# 7_PowerManagement.net
KiCad netlist of a schematic drawn in Altium Designer
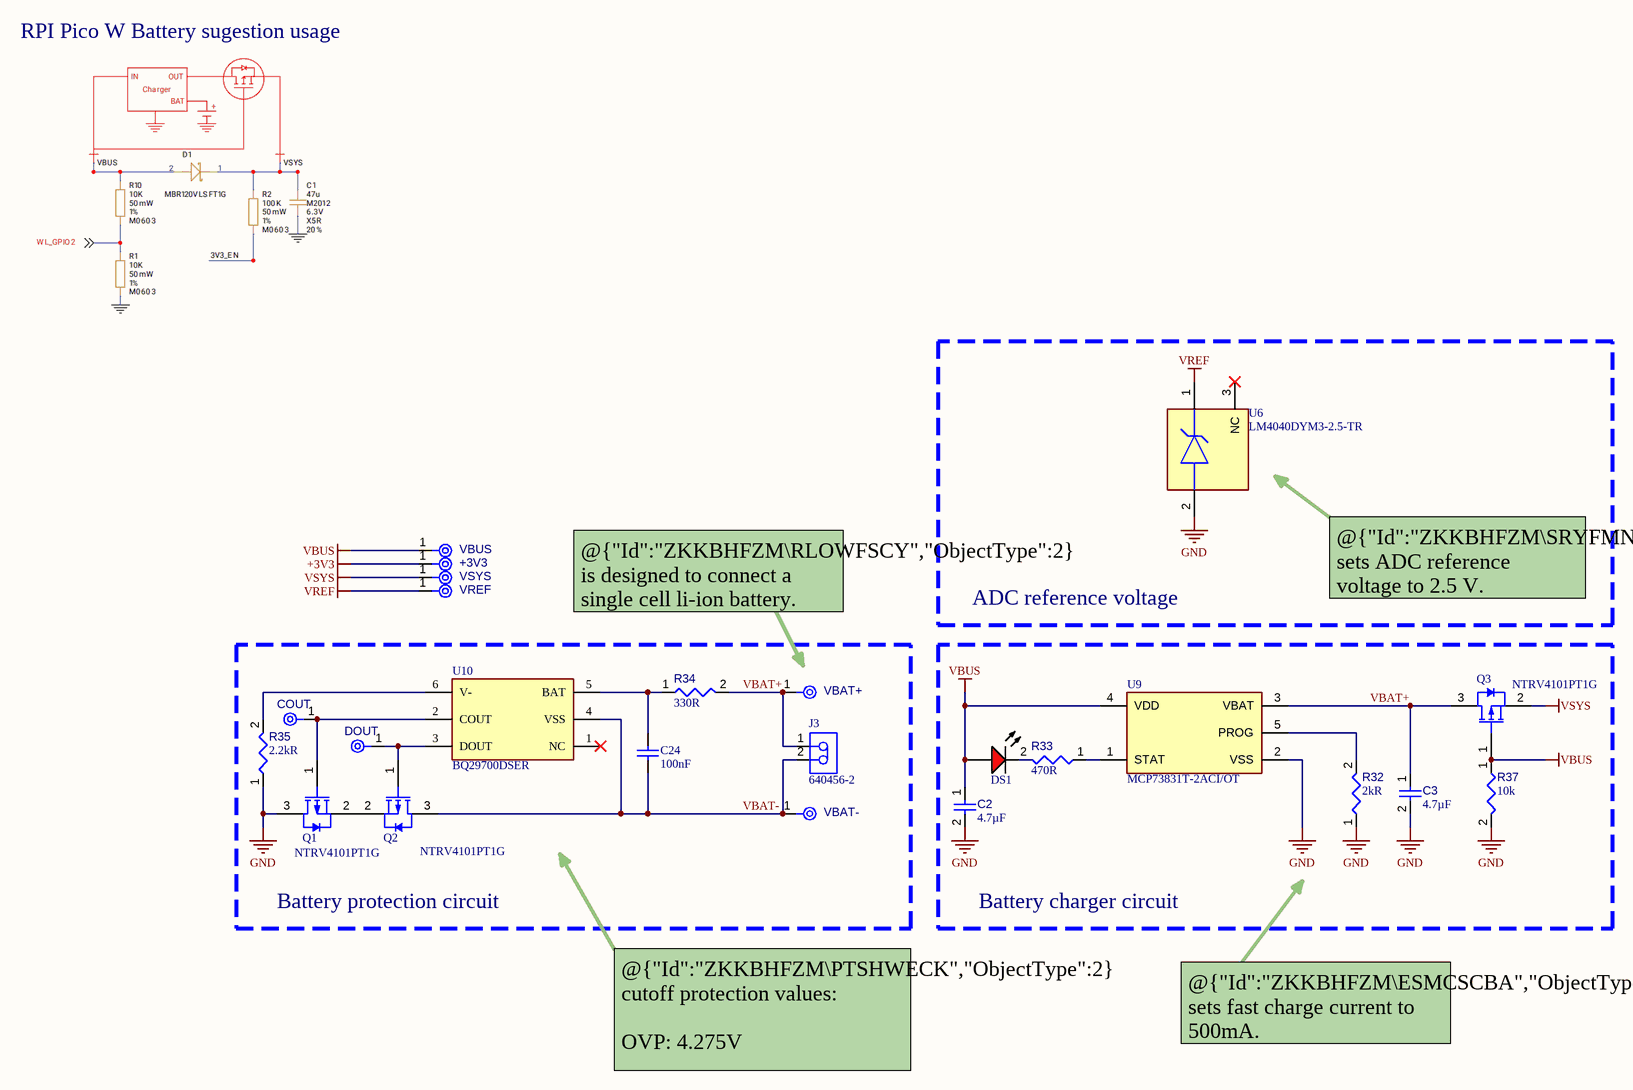
[diagram p0: [7] PowerManagement.SchDoc]

(export (version "E")
  (design (tool "Eeschema 10.0.6"))
  (components
    (comp (ref "+3V3")
      (value "TPAD6R")
      (footprint "TP06R")
      (description "0.6mm round")
      (libsource (lib "UFCG - Universidade Federal de Campina Grande") (part "CMP-001-0001-4"))
    )
    (comp (ref "C2")
      (value "4.7µF")
      (footprint "CAPC0603(1608)100_L")
      (description "Chip Capacitor, 4.7µF +/-20%, 10V, 0603, Thickness 1 mm")
      (fields (field (name "TOLERANCE") "10%") (field (name "Comment") "Capacitor 4.7µF +/-20% 10V 0603"))
      (libsource (lib "UFCG - Universidade Federal de Campina Grande") (part "CAP-NP-2"))
    )
    (comp (ref "C3")
      (value "4.7µF")
      (footprint "CAPC0603(1608)100_L")
      (description "Chip Capacitor, 4.7µF +/-20%, 10V, 0603, Thickness 1 mm")
      (fields (field (name "TOLERANCE") "10%") (field (name "Comment") "Capacitor 4.7µF +/-20% 10V 0603"))
      (libsource (lib "UFCG - Universidade Federal de Campina Grande") (part "CAP-NP-2"))
    )
    (comp (ref "C24")
      (value "100nF")
      (footprint "CAPC0603(1608)100_L")
      (description "Multilayer Ceramic Capacitor, 0.1 uF, 16 V, ± 20%, X7R, 0603 [1608 Metric]")
      (fields (field (name "TOLERANCE") "20%") (field (name "Comment") "VJ0603Y104MXJCW1BC"))
      (libsource (lib "UFCG - Universidade Federal de Campina Grande") (part "CAP"))
    )
    (comp (ref "COUT")
      (value "TPAD6R")
      (footprint "TP06R")
      (description "0.6mm round")
      (libsource (lib "UFCG - Universidade Federal de Campina Grande") (part "CMP-001-0001-4"))
    )
    (comp (ref "DOUT")
      (value "TPAD6R")
      (footprint "TP06R")
      (description "0.6mm round")
      (libsource (lib "UFCG - Universidade Federal de Campina Grande") (part "CMP-001-0001-4"))
    )
    (comp (ref "DS1")
      (value "19-217/R6C-AL1M2VY/3T")
      (footprint "EVRL-0603-2_V")
      (description "Chip LED, Red, 5 V, 25 mA, -40 to 85 degC, 2-Pin SMD (0603), RoHS, Tape and Reel")
      (fields (field (name "MANUFACTURER") "Everlight Electronics"))
      (libsource (lib "UFCG - Universidade Federal de Campina Grande") (part "LED-RED-AK-2"))
    )
    (comp (ref "J3")
      (value "640456-2")
      (footprint "TECO-640456-2_V")
      (description "Connector 250V AC/DC 5A 2P 1 Row PCB - Vertical Mounting Polyester White")
      (libsource (lib "UFCG - Universidade Federal de Campina Grande") (part "CN-2P-F-QF2"))
    )
    (comp (ref "Q1")
      (value "NTRV4101PT1G")
      (footprint "ONSC-SOT-23-3-318-08_V")
      (description "NTRV4101PT1G P-channel MOSFET Transistor; 1.7 A; 20 V; 3-Pin SOT-23")
      (libsource (lib "UFCG - Universidade Federal de Campina Grande") (part "ONSC-PMOS-G1S2D3-3_D"))
    )
    (comp (ref "Q2")
      (value "NTRV4101PT1G")
      (footprint "ONSC-SOT-23-3-318-08_V")
      (description "NTRV4101PT1G P-channel MOSFET Transistor; 1.7 A; 20 V; 3-Pin SOT-23")
      (libsource (lib "UFCG - Universidade Federal de Campina Grande") (part "ONSC-PMOS-G1S2D3-3_D"))
    )
    (comp (ref "Q3")
      (value "NTRV4101PT1G")
      (footprint "ONSC-SOT-23-3-318-08_V")
      (description "NTRV4101PT1G P-channel MOSFET Transistor; 1.7 A; 20 V; 3-Pin SOT-23")
      (libsource (lib "UFCG - Universidade Federal de Campina Grande") (part "ONSC-PMOS-G1S2D3-3_D"))
    )
    (comp (ref "R32")
      (value "2kR")
      (footprint "RESC0603(1608)_L")
      (description "SMD Chip Resistor, 2 kOhm, ï¿½ 1%, 100 mW, 0603 [1608 Metric], Thick Film, Precision")
      (fields (field (name "TOLERANCE") "1%") (field (name "Comment") "ERJ-3EKF2001V"))
      (libsource (lib "UFCG - Universidade Federal de Campina Grande") (part "RES-2"))
    )
    (comp (ref "R33")
      (value "470R")
      (footprint "RESC0603(1608)_L")
      (description "Res Thick Film 0603 470 Ohm 5% 0.1W(1/10W) ±200ppm/°C Pad SMD Automotive T/R")
      (fields (field (name "TOLERANCE") "5%") (field (name "Comment") "CRCW0603470RJNEA"))
      (libsource (lib "UFCG - Universidade Federal de Campina Grande") (part "RES-2"))
    )
    (comp (ref "R34")
      (value "330R")
      (footprint "RESC0603(1608)_L")
      (description "SMD Chip Resistor, 330 Ohm, ± 1%, 100 mW, 0603 [1608 Metric], Thick Film, Precision")
      (fields (field (name "TOLERANCE") "1%") (field (name "Comment") "ERJ-3EKF3300V"))
      (libsource (lib "UFCG - Universidade Federal de Campina Grande") (part "RES-2"))
    )
    (comp (ref "R35")
      (value "2.2kR")
      (footprint "RESC0603(1608)_L")
      (description "SMD Chip Resistor, 2.2 kOhm, ± 1%, 100 mW, 0603 [1608 Metric], Thick Film, General Purpose")
      (fields (field (name "TOLERANCE") "1%") (field (name "Comment") "CRCW06032K20FKEA"))
      (libsource (lib "UFCG - Universidade Federal de Campina Grande") (part "RES-2"))
    )
    (comp (ref "R37")
      (value "10k")
      (footprint "RESC0603(1608)_L")
      (description "Chip Resistor, 10 KOhm, +/- 1%, 01 W, -55 to 155 degC, 0603 (1608 Metric)")
      (fields (field (name "POWER") "100mW") (field (name "TOLERANCE") "1%"))
      (libsource (lib "UFCG - Universidade Federal de Campina Grande") (part "RES-2"))
    )
    (comp (ref "U6")
      (value "LM4040DYM3-2.5-TR")
      (footprint "FP-SOT23-3LD-PL-1-IPC_A")
      (description "LM4040 Series 2.5 V ±1 % Precision Micropower Shunt Voltage Reference - SOT-23")
      (fields (field (name "TOLERANCE") "1%"))
      (libsource (lib "UFCG - Universidade Federal de Campina Grande") (part "91f0ca7be5727739b22823fb575e884"))
    )
    (comp (ref "U9")
      (value "MCP73831T-2ACI/OT")
      (footprint "FP-C04-091-OT-MFG")
      (description "MCP73831 Series Single-Cell Li-Ion/Li-Polymer Battery Charge Controller SOT-23-5")
      (libsource (lib "UFCG - Universidade Federal de Campina Grande") (part "61f5a3bb3429d9e0caadea342aa3b19"))
    )
    (comp (ref "U10")
      (value "BQ29700DSER")
      (footprint "FP-DSE0006A-MFG")
      (description "Li-Ion/Li Polymer Advanced Single-Cell Battery Protector IC Family 6-WSON -40 to 85")
      (libsource (lib "UFCG - Universidade Federal de Campina Grande") (part "cb1a035e2e9bf15fad579f9d3aca51e"))
    )
    (comp (ref "VBAT+")
      (value "TPAD6R")
      (footprint "TP06R")
      (description "0.6mm round")
      (libsource (lib "UFCG - Universidade Federal de Campina Grande") (part "CMP-001-0001-4"))
    )
    (comp (ref "VBAT-")
      (value "TPAD6R")
      (footprint "TP06R")
      (description "0.6mm round")
      (libsource (lib "UFCG - Universidade Federal de Campina Grande") (part "CMP-001-0001-4"))
    )
    (comp (ref "VBUS")
      (value "TPAD6R")
      (footprint "TP06R")
      (description "0.6mm round")
      (libsource (lib "UFCG - Universidade Federal de Campina Grande") (part "CMP-001-0001-4"))
    )
    (comp (ref "VREF")
      (value "TPAD6R")
      (footprint "TP06R")
      (description "0.6mm round")
      (libsource (lib "UFCG - Universidade Federal de Campina Grande") (part "CMP-001-0001-4"))
    )
    (comp (ref "VSYS")
      (value "TPAD6R")
      (footprint "TP06R")
      (description "0.6mm round")
      (libsource (lib "UFCG - Universidade Federal de Campina Grande") (part "CMP-001-0001-4"))
    )
  )
  (nets
    (net (code "1") (name "+3V3") (class "Default")
      (node (ref "+3V3") (pin "1") (pinfunction "TP_1") (pintype "passive"))
    )
    (net (code "2") (name "/VBAT+") (class "Default")
      (node (ref "C3") (pin "1") (pinfunction "1_1") (pintype "passive"))
      (node (ref "J3") (pin "1") (pinfunction "1_1") (pintype "passive"))
      (node (ref "Q3") (pin "3") (pinfunction "D_3") (pintype "passive"))
      (node (ref "R34") (pin "2") (pinfunction "2_2") (pintype "passive"))
      (node (ref "U9") (pin "3") (pinfunction "VBAT_3") (pintype "power_in"))
      (node (ref "VBAT+") (pin "1") (pinfunction "TP_1") (pintype "passive"))
    )
    (net (code "3") (name "/VBAT-") (class "Default")
      (node (ref "C24") (pin "1") (pinfunction "1_1") (pintype "passive"))
      (node (ref "J3") (pin "2") (pinfunction "2_2") (pintype "passive"))
      (node (ref "Q2") (pin "3") (pinfunction "D_3") (pintype "passive"))
      (node (ref "U10") (pin "4") (pinfunction "VSS_4") (pintype "power_in"))
      (node (ref "VBAT-") (pin "1") (pinfunction "TP_1") (pintype "passive"))
    )
    (net (code "4") (name "GND") (class "Default")
      (node (ref "C2") (pin "2") (pinfunction "2_2") (pintype "passive"))
      (node (ref "C3") (pin "2") (pinfunction "2_2") (pintype "passive"))
      (node (ref "Q1") (pin "3") (pinfunction "D_3") (pintype "passive"))
      (node (ref "R32") (pin "1") (pinfunction "1_1") (pintype "passive"))
      (node (ref "R35") (pin "1") (pinfunction "1_1") (pintype "passive"))
      (node (ref "R37") (pin "2") (pinfunction "2_2") (pintype "passive"))
      (node (ref "U6") (pin "2") (pinfunction "-_2") (pintype "passive"))
      (node (ref "U9") (pin "2") (pinfunction "VSS_2") (pintype "power_in"))
    )
    (net (code "5") (name "Net-(COUT-TP)") (class "Default")
      (node (ref "COUT") (pin "1") (pinfunction "TP_1") (pintype "passive"))
      (node (ref "Q1") (pin "1") (pinfunction "G_1") (pintype "passive"))
      (node (ref "U10") (pin "2") (pinfunction "COUT_2") (pintype "passive"))
    )
    (net (code "6") (name "Net-(DOUT-TP)") (class "Default")
      (node (ref "DOUT") (pin "1") (pinfunction "TP_1") (pintype "passive"))
      (node (ref "Q2") (pin "1") (pinfunction "G_1") (pintype "passive"))
      (node (ref "U10") (pin "3") (pinfunction "DOUT_3") (pintype "passive"))
    )
    (net (code "7") (name "Net-(DS1-K)") (class "Default")
      (node (ref "DS1") (pin "2") (pinfunction "K_2") (pintype "passive"))
      (node (ref "R33") (pin "2") (pinfunction "2_2") (pintype "passive"))
    )
    (net (code "8") (name "Net-(Q1-S)") (class "Default")
      (node (ref "Q1") (pin "2") (pinfunction "S_2") (pintype "passive"))
      (node (ref "Q2") (pin "2") (pinfunction "S_2") (pintype "passive"))
    )
    (net (code "9") (name "Net-(U9-PROG)") (class "Default")
      (node (ref "R32") (pin "2") (pinfunction "2_2") (pintype "passive"))
      (node (ref "U9") (pin "5") (pinfunction "PROG_5") (pintype "passive"))
    )
    (net (code "10") (name "Net-(U9-STAT)") (class "Default")
      (node (ref "R33") (pin "1") (pinfunction "1_1") (pintype "passive"))
      (node (ref "U9") (pin "1") (pinfunction "STAT_1") (pintype "passive"))
    )
    (net (code "11") (name "Net-(U10-BAT)") (class "Default")
      (node (ref "C24") (pin "2") (pinfunction "2_2") (pintype "passive"))
      (node (ref "R34") (pin "1") (pinfunction "1_1") (pintype "passive"))
      (node (ref "U10") (pin "5") (pinfunction "BAT_5") (pintype "power_in"))
    )
    (net (code "12") (name "Net-(U10-V-)") (class "Default")
      (node (ref "R35") (pin "2") (pinfunction "2_2") (pintype "passive"))
      (node (ref "U10") (pin "6") (pinfunction "V-_6") (pintype "passive"))
    )
    (net (code "13") (name "VBUS") (class "Default")
      (node (ref "C2") (pin "1") (pinfunction "1_1") (pintype "passive"))
      (node (ref "DS1") (pin "1") (pinfunction "A_1") (pintype "passive"))
      (node (ref "Q3") (pin "1") (pinfunction "G_1") (pintype "passive"))
      (node (ref "R37") (pin "1") (pinfunction "1_1") (pintype "passive"))
      (node (ref "U9") (pin "4") (pinfunction "VDD_4") (pintype "power_in"))
      (node (ref "VBUS") (pin "1") (pinfunction "TP_1") (pintype "passive"))
    )
    (net (code "14") (name "VREF") (class "Default")
      (node (ref "U6") (pin "1") (pinfunction "+_1") (pintype "passive"))
      (node (ref "VREF") (pin "1") (pinfunction "TP_1") (pintype "passive"))
    )
    (net (code "15") (name "VSYS") (class "Default")
      (node (ref "Q3") (pin "2") (pinfunction "S_2") (pintype "passive"))
      (node (ref "VSYS") (pin "1") (pinfunction "TP_1") (pintype "passive"))
    )
    (net (code "16") (name "unconnected-(U6-NC-Pad3)") (class "Default")
      (node (ref "U6") (pin "3") (pinfunction "NC_3") (pintype "passive+no_connect"))
    )
    (net (code "17") (name "unconnected-(U10-NC-Pad1)") (class "Default")
      (node (ref "U10") (pin "1") (pinfunction "NC_1") (pintype "passive+no_connect"))
    )
  )
)
